# remote_25_45_85.net
KiCad netlist of a schematic drawn in EAGLE
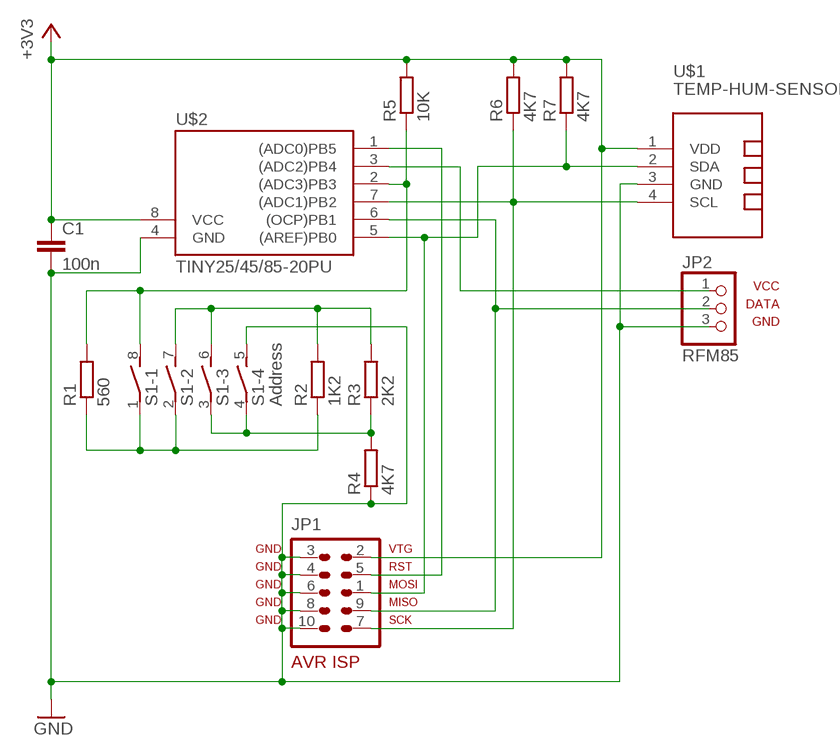
[diagram p0: schematic, sheet 1]

(export (version "E")
  (design (tool "Eeschema 10.0.6"))
  (components
    (comp (ref "C1")
      (value "100n")
      (footprint "eagle-import:C025-025X050")
      (libsource (lib "eagle-import") (part "C-EU025-025X050"))
    )
    (comp (ref "JP1")
      (value "AVR-ISP-10")
      (footprint "eagle-import:AVR-ISP-10")
      (libsource (lib "eagle-import") (part "AVR-ISP-10"))
    )
    (comp (ref "JP2")
      (value "RFM85")
      (footprint "eagle-import:1X03")
      (libsource (lib "eagle-import") (part "PINHD-1X3"))
    )
    (comp (ref "R1")
      (value "560")
      (footprint "eagle-import:0204_7")
      (libsource (lib "eagle-import") (part "R-EU_0204/7"))
    )
    (comp (ref "R2")
      (value "1K2")
      (footprint "eagle-import:0204_7")
      (libsource (lib "eagle-import") (part "R-EU_0204/7"))
    )
    (comp (ref "R3")
      (value "2K2")
      (footprint "eagle-import:0204_7")
      (libsource (lib "eagle-import") (part "R-EU_0204/7"))
    )
    (comp (ref "R4")
      (value "4K7")
      (footprint "eagle-import:0204_7")
      (libsource (lib "eagle-import") (part "R-EU_0204/7"))
    )
    (comp (ref "R5")
      (value "10K")
      (footprint "eagle-import:0204_7")
      (libsource (lib "eagle-import") (part "R-EU_0204/7"))
    )
    (comp (ref "R6")
      (value "4K7")
      (footprint "eagle-import:0204_7")
      (libsource (lib "eagle-import") (part "R-EU_0204/7"))
    )
    (comp (ref "R7")
      (value "4K7")
      (footprint "eagle-import:0204_7")
      (libsource (lib "eagle-import") (part "R-EU_0204/7"))
    )
    (comp (ref "S1")
      (value "Address")
      (footprint "eagle-import:DIP04S")
      (libsource (lib "eagle-import") (part "DIP04S"))
    )
    (comp (ref "U$1")
      (value "TEMP-HUM-SENSOR")
      (footprint "eagle-import:TEMP-HUM-SENSOR-AM2322")
      (libsource (lib "eagle-import") (part "TEMP-HUM-SENSOR-AM2322"))
    )
    (comp (ref "U$2")
      (value "TINY25/45/85-20PU")
      (footprint "eagle-import:SOIC8")
      (libsource (lib "eagle-import") (part "TINY25/45/85-20SU"))
    )
  )
  (nets
    (net (code "1") (name "+3V3") (class "Default")
      (node (ref "C1") (pin "1") (pinfunction "1_1") (pintype "passive"))
      (node (ref "JP1") (pin "2") (pinfunction "2_2") (pintype "passive"))
      (node (ref "R5") (pin "2") (pinfunction "2_2") (pintype "passive"))
      (node (ref "R6") (pin "2") (pinfunction "2_2") (pintype "passive"))
      (node (ref "R7") (pin "2") (pinfunction "2_2") (pintype "passive"))
      (node (ref "U$1") (pin "1") (pinfunction "VDD_1") (pintype "power_in"))
      (node (ref "U$2") (pin "8") (pinfunction "VCC_8") (pintype "power_in"))
    )
    (net (code "2") (name "GND") (class "Default")
      (node (ref "C1") (pin "2") (pinfunction "2_2") (pintype "passive"))
      (node (ref "JP1") (pin "10") (pinfunction "10_10") (pintype "passive"))
      (node (ref "JP1") (pin "3") (pinfunction "3_3") (pintype "passive"))
      (node (ref "JP1") (pin "4") (pinfunction "4_4") (pintype "passive"))
      (node (ref "JP1") (pin "6") (pinfunction "6_6") (pintype "passive"))
      (node (ref "JP1") (pin "8") (pinfunction "8_8") (pintype "passive"))
      (node (ref "JP2") (pin "3") (pinfunction "3_3") (pintype "passive"))
      (node (ref "R4") (pin "1") (pinfunction "1_1") (pintype "passive"))
      (node (ref "S1") (pin "5") (pinfunction "2_5") (pintype "passive"))
      (node (ref "U$1") (pin "3") (pinfunction "GND_3") (pintype "power_in"))
      (node (ref "U$2") (pin "4") (pinfunction "GND_4") (pintype "power_in"))
    )
    (net (code "3") (name "Net-(S1A-2)") (class "Default")
      (node (ref "R1") (pin "2") (pinfunction "2_2") (pintype "passive"))
      (node (ref "R5") (pin "1") (pinfunction "1_1") (pintype "passive"))
      (node (ref "S1") (pin "8") (pinfunction "2_8") (pintype "passive"))
      (node (ref "U$2") (pin "2") (pinfunction "(ADC3)PB3_2") (pintype "bidirectional"))
    )
    (net (code "4") (name "Net-(S1B-1)") (class "Default")
      (node (ref "R1") (pin "1") (pinfunction "1_1") (pintype "passive"))
      (node (ref "R2") (pin "1") (pinfunction "1_1") (pintype "passive"))
      (node (ref "S1") (pin "1") (pinfunction "1_1") (pintype "passive"))
      (node (ref "S1") (pin "2") (pinfunction "1_2") (pintype "passive"))
    )
    (net (code "5") (name "Net-(S1B-2)") (class "Default")
      (node (ref "R2") (pin "2") (pinfunction "2_2") (pintype "passive"))
      (node (ref "R3") (pin "2") (pinfunction "2_2") (pintype "passive"))
      (node (ref "S1") (pin "6") (pinfunction "2_6") (pintype "passive"))
      (node (ref "S1") (pin "7") (pinfunction "2_7") (pintype "passive"))
    )
    (net (code "6") (name "Net-(S1C-1)") (class "Default")
      (node (ref "R3") (pin "1") (pinfunction "1_1") (pintype "passive"))
      (node (ref "R4") (pin "2") (pinfunction "2_2") (pintype "passive"))
      (node (ref "S1") (pin "3") (pinfunction "1_3") (pintype "passive"))
      (node (ref "S1") (pin "4") (pinfunction "1_4") (pintype "passive"))
    )
    (net (code "7") (name "Net-(U$1-SCL)") (class "Default")
      (node (ref "JP1") (pin "7") (pinfunction "7_7") (pintype "passive"))
      (node (ref "R6") (pin "1") (pinfunction "1_1") (pintype "passive"))
      (node (ref "U$1") (pin "4") (pinfunction "SCL_4") (pintype "bidirectional"))
      (node (ref "U$2") (pin "7") (pinfunction "(ADC1)PB2_7") (pintype "bidirectional"))
    )
    (net (code "8") (name "Net-(U$1-SDA)") (class "Default")
      (node (ref "JP1") (pin "1") (pinfunction "1_1") (pintype "passive"))
      (node (ref "R7") (pin "1") (pinfunction "1_1") (pintype "passive"))
      (node (ref "U$1") (pin "2") (pinfunction "SDA_2") (pintype "bidirectional"))
      (node (ref "U$2") (pin "5") (pinfunction "(AREF)PB0_5") (pintype "bidirectional"))
    )
    (net (code "9") (name "Net-(U$2-(ADC0)PB5)") (class "Default")
      (node (ref "JP1") (pin "5") (pinfunction "5_5") (pintype "passive"))
      (node (ref "U$2") (pin "1") (pinfunction "(ADC0)PB5_1") (pintype "bidirectional"))
    )
    (net (code "10") (name "Net-(U$2-(ADC2)PB4)") (class "Default")
      (node (ref "JP2") (pin "1") (pinfunction "1_1") (pintype "passive"))
      (node (ref "U$2") (pin "3") (pinfunction "(ADC2)PB4_3") (pintype "bidirectional"))
    )
    (net (code "11") (name "Net-(U$2-(OCP)PB1)") (class "Default")
      (node (ref "JP1") (pin "9") (pinfunction "9_9") (pintype "passive"))
      (node (ref "JP2") (pin "2") (pinfunction "2_2") (pintype "passive"))
      (node (ref "U$2") (pin "6") (pinfunction "(OCP)PB1_6") (pintype "bidirectional"))
    )
  )
)
